# 7_-POWER_DCDC_3V3.net
KiCad netlist of a schematic drawn in Altium Designer
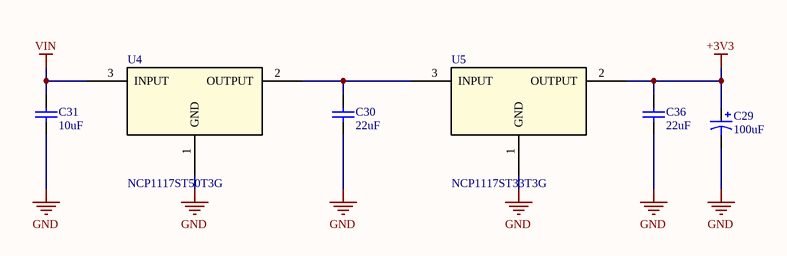
[diagram p0: [7]-POWER_DCDC_3V3.SchDoc]

(export (version "E")
  (design (tool "Eeschema 10.0.6"))
  (components
    (comp (ref "C29")
      (value "100uF")
      (footprint "CAPAE6553X55M")
      (description "CAP ALUM 100UF 20% 10V SMD")
      (fields (field (name "TOLERANCE") "20%"))
      (libsource (lib "bitsnio") (part "EEE-1AA101WR"))
    )
    (comp (ref "C30")
      (value "22uF")
      (footprint "CAPC2012N")
      (description "CAP CER 22UF 6.3V X5R 0805")
      (fields
        (field (name "PCN PART NUMBER") "X5R, X7R Dielectrics 23/Jan/2008")
        (field (name "TOLERANCE") "±20%")
      )
      (libsource (lib "bitsnio") (part "JMK212BJ226MG-T"))
    )
    (comp (ref "C31")
      (value "10uF")
      (footprint "CAPC2012N")
      (description "CAP CER 10UF 25V X5R 0805")
      (fields (field (name "TOLERANCE") "±10%"))
      (libsource (lib "bitsnio") (part "GRM21BR61E106KA73L"))
    )
    (comp (ref "C36")
      (value "22uF")
      (footprint "CAPC2012N")
      (description "CAP CER 22UF 6.3V X5R 0805")
      (fields
        (field (name "PCN PART NUMBER") "X5R, X7R Dielectrics 23/Jan/2008")
        (field (name "TOLERANCE") "±20%")
      )
      (libsource (lib "bitsnio") (part "JMK212BJ226MG-T"))
    )
    (comp (ref "U4")
      (value "NCP1117ST50T3G")
      (footprint "SOT230P700X180-4N")
      (description "LDO Regulator Pos 5V 1A 4-Pin(3+Tab) SOT-223 T/R / IC REG LDO 5V 1A SOT223")
      (fields (field (name "TOLERANCE") "1%"))
      (libsource (lib "bitsnio") (part "NCP1117ST50T3G"))
    )
    (comp (ref "U5")
      (value "NCP1117ST33T3G")
      (footprint "SOT230P700X180-4N")
      (description "1.0 A Positive LDO Linear Voltage Regulator (Fixed and Adjustable), V out : 3.3 V")
      (libsource (lib "bitsnio") (part "NCP1117ST33T3G"))
    )
  )
  (nets
    (net (code "1") (name "+3V3") (class "Default")
      (node (ref "C29") (pin "1") (pinfunction "1_1") (pintype "passive"))
      (node (ref "C36") (pin "2") (pinfunction "2_2") (pintype "passive"))
      (node (ref "U5") (pin "2") (pinfunction "OUTPUT_2") (pintype "passive"))
    )
    (net (code "2") (name "GND") (class "Default")
      (node (ref "C29") (pin "2") (pinfunction "2_2") (pintype "passive"))
      (node (ref "C30") (pin "1") (pinfunction "1_1") (pintype "passive"))
      (node (ref "C31") (pin "1") (pinfunction "1_1") (pintype "passive"))
      (node (ref "C36") (pin "1") (pinfunction "1_1") (pintype "passive"))
      (node (ref "U4") (pin "1") (pinfunction "GND_1") (pintype "passive"))
      (node (ref "U5") (pin "1") (pinfunction "GND_1") (pintype "passive"))
    )
    (net (code "3") (name "Net-(U4-OUTPUT)") (class "Default")
      (node (ref "C30") (pin "2") (pinfunction "2_2") (pintype "passive"))
      (node (ref "U4") (pin "2") (pinfunction "OUTPUT_2") (pintype "passive"))
      (node (ref "U5") (pin "3") (pinfunction "INPUT_3") (pintype "passive"))
    )
    (net (code "4") (name "VIN") (class "Default")
      (node (ref "C31") (pin "2") (pinfunction "2_2") (pintype "passive"))
      (node (ref "U4") (pin "3") (pinfunction "INPUT_3") (pintype "passive"))
    )
  )
)
